# gatedriver_trafo_sma.net
KiCad netlist of a schematic drawn in EAGLE
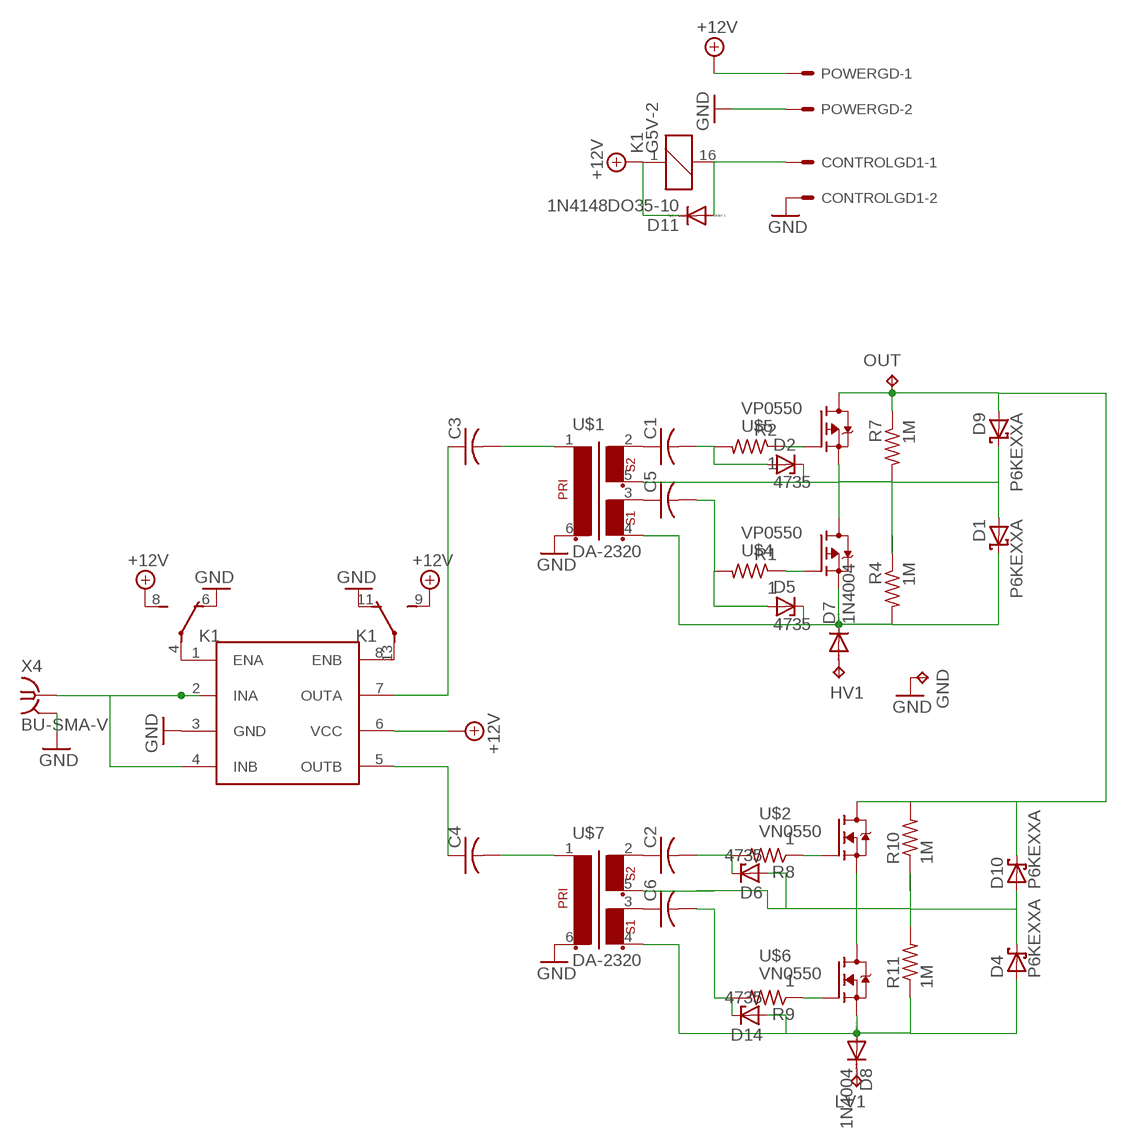
[diagram p0: schematic, sheet 1]

(export (version "E")
  (design (tool "Eeschema 10.0.6"))
  (components
    (comp (ref "C1")
      (value "C-US050-055X075")
      (footprint "eagle-import:C050-055X075")
      (libsource (lib "eagle-import") (part "C-US050-055X075"))
    )
    (comp (ref "C2")
      (value "C-US050-055X075")
      (footprint "eagle-import:C050-055X075")
      (libsource (lib "eagle-import") (part "C-US050-055X075"))
    )
    (comp (ref "C3")
      (value "C-US050-055X075")
      (footprint "eagle-import:C050-055X075")
      (libsource (lib "eagle-import") (part "C-US050-055X075"))
    )
    (comp (ref "C4")
      (value "C-US050-055X075")
      (footprint "eagle-import:C050-055X075")
      (libsource (lib "eagle-import") (part "C-US050-055X075"))
    )
    (comp (ref "C5")
      (value "C-US050-055X075")
      (footprint "eagle-import:C050-055X075")
      (libsource (lib "eagle-import") (part "C-US050-055X075"))
    )
    (comp (ref "C6")
      (value "C-US050-055X075")
      (footprint "eagle-import:C050-055X075")
      (libsource (lib "eagle-import") (part "C-US050-055X075"))
    )
    (comp (ref "CONTROLGD1")
      (value "KK-156-2")
      (footprint "eagle-import:KK-156-2")
      (libsource (lib "eagle-import") (part "KK-156-2"))
    )
    (comp (ref "D1")
      (value "P6KEXXA")
      (footprint "eagle-import:C1702-15")
      (libsource (lib "eagle-import") (part "P6KEXXA"))
    )
    (comp (ref "D2")
      (value "4735")
      (footprint "eagle-import:ZDIO-10")
      (libsource (lib "eagle-import") (part "ZENER-DIODEZD-10"))
    )
    (comp (ref "D4")
      (value "P6KEXXA")
      (footprint "eagle-import:C1702-15")
      (libsource (lib "eagle-import") (part "P6KEXXA"))
    )
    (comp (ref "D5")
      (value "4735")
      (footprint "eagle-import:ZDIO-10")
      (libsource (lib "eagle-import") (part "ZENER-DIODEZD-10"))
    )
    (comp (ref "D6")
      (value "4735")
      (footprint "eagle-import:ZDIO-10")
      (libsource (lib "eagle-import") (part "ZENER-DIODEZD-10"))
    )
    (comp (ref "D7")
      (value "1N4004")
      (footprint "eagle-import:DO41-10")
      (libsource (lib "eagle-import") (part "1N4004"))
    )
    (comp (ref "D8")
      (value "1N4004")
      (footprint "eagle-import:DO41-10")
      (libsource (lib "eagle-import") (part "1N4004"))
    )
    (comp (ref "D9")
      (value "P6KEXXA")
      (footprint "eagle-import:C1702-15")
      (libsource (lib "eagle-import") (part "P6KEXXA"))
    )
    (comp (ref "D10")
      (value "P6KEXXA")
      (footprint "eagle-import:C1702-15")
      (libsource (lib "eagle-import") (part "P6KEXXA"))
    )
    (comp (ref "D11")
      (value "1N4148DO35-10")
      (footprint "eagle-import:DO35-10")
      (libsource (lib "eagle-import") (part "1N4148DO35-10"))
    )
    (comp (ref "D14")
      (value "4735")
      (footprint "eagle-import:ZDIO-10")
      (libsource (lib "eagle-import") (part "ZENER-DIODEZD-10"))
    )
    (comp (ref "GND")
      (value "TPPAD1-20Y")
      (footprint "eagle-import:P1-20Y")
      (libsource (lib "eagle-import") (part "TPPAD1-20Y"))
    )
    (comp (ref "HV1")
      (value "TPPAD1-20Y")
      (footprint "eagle-import:P1-20Y")
      (libsource (lib "eagle-import") (part "TPPAD1-20Y"))
    )
    (comp (ref "K1")
      (value "G5V-2")
      (footprint "eagle-import:G5V-2")
      (fields (field (name "MPN") "G5V-2 5DC"))
      (libsource (lib "eagle-import") (part "G5V-2"))
    )
    (comp (ref "LV1")
      (value "TPPAD1-20Y")
      (footprint "eagle-import:P1-20Y")
      (libsource (lib "eagle-import") (part "TPPAD1-20Y"))
    )
    (comp (ref "OUT")
      (value "TPPAD1-20Y")
      (footprint "eagle-import:P1-20Y")
      (libsource (lib "eagle-import") (part "TPPAD1-20Y"))
    )
    (comp (ref "POWERGD")
      (value "KK-156-2")
      (footprint "eagle-import:KK-156-2")
      (libsource (lib "eagle-import") (part "KK-156-2"))
    )
    (comp (ref "R1")
      (value "1")
      (footprint "eagle-import:0207_12")
      (libsource (lib "eagle-import") (part "R-US_0207/12"))
    )
    (comp (ref "R2")
      (value "1")
      (footprint "eagle-import:0207_12")
      (libsource (lib "eagle-import") (part "R-US_0207/12"))
    )
    (comp (ref "R4")
      (value "1M")
      (footprint "eagle-import:0207_12")
      (libsource (lib "eagle-import") (part "R-US_0207/12"))
    )
    (comp (ref "R7")
      (value "1M")
      (footprint "eagle-import:0207_12")
      (libsource (lib "eagle-import") (part "R-US_0207/12"))
    )
    (comp (ref "R8")
      (value "1")
      (footprint "eagle-import:0207_12")
      (libsource (lib "eagle-import") (part "R-US_0207/12"))
    )
    (comp (ref "R9")
      (value "1")
      (footprint "eagle-import:0207_12")
      (libsource (lib "eagle-import") (part "R-US_0207/12"))
    )
    (comp (ref "R10")
      (value "1M")
      (footprint "eagle-import:0207_12")
      (libsource (lib "eagle-import") (part "R-US_0207/12"))
    )
    (comp (ref "R11")
      (value "1M")
      (footprint "eagle-import:0207_12")
      (libsource (lib "eagle-import") (part "R-US_0207/12"))
    )
    (comp (ref "U$1")
      (value "DA-2320")
      (footprint "eagle-import:DIL06")
      (libsource (lib "eagle-import") (part "DA-2320"))
    )
    (comp (ref "U$2")
      (value "VN0550")
      (footprint "eagle-import:TO92-")
      (libsource (lib "eagle-import") (part "VN0550"))
    )
    (comp (ref "U$3")
      (value "UCC27425")
      (footprint "eagle-import:DIL08")
      (libsource (lib "eagle-import") (part "UCC27425"))
    )
    (comp (ref "U$4")
      (value "VP0550")
      (footprint "eagle-import:TO92-")
      (libsource (lib "eagle-import") (part "VP0550"))
    )
    (comp (ref "U$5")
      (value "VP0550")
      (footprint "eagle-import:TO92-")
      (libsource (lib "eagle-import") (part "VP0550"))
    )
    (comp (ref "U$6")
      (value "VN0550")
      (footprint "eagle-import:TO92-")
      (libsource (lib "eagle-import") (part "VN0550"))
    )
    (comp (ref "U$7")
      (value "DA-2320")
      (footprint "eagle-import:DIL06")
      (libsource (lib "eagle-import") (part "DA-2320"))
    )
    (comp (ref "X4")
      (value "BU-SMA-V")
      (footprint "eagle-import:BU-SMA-V")
      (libsource (lib "eagle-import") (part "BU-SMA-V"))
    )
  )
  (nets
    (net (code "1") (name "+12V") (class "Default")
      (node (ref "D11") (pin "C") (pinfunction "C_C") (pintype "passive"))
      (node (ref "K1") (pin "1") (pinfunction "1_1") (pintype "passive"))
      (node (ref "K1") (pin "8") (pinfunction "S_8") (pintype "passive"))
      (node (ref "K1") (pin "9") (pinfunction "S_9") (pintype "passive"))
      (node (ref "POWERGD") (pin "1") (pinfunction "S_1") (pintype "passive"))
      (node (ref "U$3") (pin "6") (pinfunction "VCC_6") (pintype "bidirectional"))
    )
    (net (code "2") (name "/N$17") (class "Default")
      (node (ref "D1") (pin "C") (pinfunction "C_C") (pintype "passive"))
      (node (ref "D5") (pin "C") (pinfunction "C_C") (pintype "passive"))
      (node (ref "D7") (pin "C") (pinfunction "C_C") (pintype "passive"))
      (node (ref "R4") (pin "2") (pinfunction "2_2") (pintype "passive"))
      (node (ref "U$1") (pin "4") (pinfunction "3_4") (pintype "passive"))
      (node (ref "U$4") (pin "3") (pinfunction "S_3") (pintype "passive"))
    )
    (net (code "3") (name "GND") (class "Default")
      (node (ref "CONTROLGD1") (pin "2") (pinfunction "S_2") (pintype "passive"))
      (node (ref "GND") (pin "TP") (pinfunction "TP_TP") (pintype "input"))
      (node (ref "K1") (pin "11") (pinfunction "O_11") (pintype "passive"))
      (node (ref "K1") (pin "6") (pinfunction "O_6") (pintype "passive"))
      (node (ref "POWERGD") (pin "2") (pinfunction "S_2") (pintype "passive"))
      (node (ref "U$1") (pin "6") (pinfunction "2_6") (pintype "passive"))
      (node (ref "U$3") (pin "3") (pinfunction "GND_3") (pintype "bidirectional"))
      (node (ref "U$7") (pin "6") (pinfunction "2_6") (pintype "passive"))
      (node (ref "X4") (pin "2") (pinfunction "2_2") (pintype "passive"))
      (node (ref "X4") (pin "3") (pinfunction "2_3") (pintype "passive"))
      (node (ref "X4") (pin "4") (pinfunction "2_4") (pintype "passive"))
      (node (ref "X4") (pin "5") (pinfunction "2_5") (pintype "passive"))
    )
    (net (code "4") (name "Net-(C1-Pad2)") (class "Default")
      (node (ref "C1") (pin "2") (pinfunction "2_2") (pintype "passive"))
      (node (ref "D2") (pin "A") (pinfunction "A_A") (pintype "passive"))
      (node (ref "R2") (pin "2") (pinfunction "2_2") (pintype "passive"))
    )
    (net (code "5") (name "Net-(C2-Pad2)") (class "Default")
      (node (ref "C2") (pin "2") (pinfunction "2_2") (pintype "passive"))
      (node (ref "D6") (pin "C") (pinfunction "C_C") (pintype "passive"))
      (node (ref "R8") (pin "2") (pinfunction "2_2") (pintype "passive"))
    )
    (net (code "6") (name "Net-(C3-Pad2)") (class "Default")
      (node (ref "C3") (pin "2") (pinfunction "2_2") (pintype "passive"))
      (node (ref "U$1") (pin "1") (pinfunction "1_1") (pintype "passive"))
    )
    (net (code "7") (name "Net-(C4-Pad2)") (class "Default")
      (node (ref "C4") (pin "2") (pinfunction "2_2") (pintype "passive"))
      (node (ref "U$7") (pin "1") (pinfunction "1_1") (pintype "passive"))
    )
    (net (code "8") (name "Net-(C5-Pad2)") (class "Default")
      (node (ref "C5") (pin "2") (pinfunction "2_2") (pintype "passive"))
      (node (ref "D5") (pin "A") (pinfunction "A_A") (pintype "passive"))
      (node (ref "R1") (pin "2") (pinfunction "2_2") (pintype "passive"))
    )
    (net (code "9") (name "Net-(C6-Pad2)") (class "Default")
      (node (ref "C6") (pin "2") (pinfunction "2_2") (pintype "passive"))
      (node (ref "D14") (pin "C") (pinfunction "C_C") (pintype "passive"))
      (node (ref "R9") (pin "2") (pinfunction "2_2") (pintype "passive"))
    )
    (net (code "10") (name "Net-(CONTROLGD1A-S)") (class "Default")
      (node (ref "CONTROLGD1") (pin "1") (pinfunction "S_1") (pintype "passive"))
      (node (ref "D11") (pin "A") (pinfunction "A_A") (pintype "passive"))
      (node (ref "K1") (pin "16") (pinfunction "2_16") (pintype "passive"))
    )
    (net (code "11") (name "Net-(D7-PadA)") (class "Default")
      (node (ref "D7") (pin "A") (pinfunction "A_A") (pintype "passive"))
      (node (ref "HV1") (pin "TP") (pinfunction "TP_TP") (pintype "input"))
    )
    (net (code "12") (name "Net-(D8-PadC)") (class "Default")
      (node (ref "D8") (pin "C") (pinfunction "C_C") (pintype "passive"))
      (node (ref "LV1") (pin "TP") (pinfunction "TP_TP") (pintype "input"))
    )
    (net (code "13") (name "Net-(K1A-P)") (class "Default")
      (node (ref "K1") (pin "4") (pinfunction "P_4") (pintype "passive"))
      (node (ref "U$3") (pin "1") (pinfunction "ENA_1") (pintype "bidirectional"))
    )
    (net (code "14") (name "Net-(K1B-P)") (class "Default")
      (node (ref "K1") (pin "13") (pinfunction "P_13") (pintype "passive"))
      (node (ref "U$3") (pin "8") (pinfunction "ENB_8") (pintype "bidirectional"))
    )
    (net (code "15") (name "Net-(U$1-4)") (class "Default")
      (node (ref "C5") (pin "1") (pinfunction "1_1") (pintype "passive"))
      (node (ref "U$1") (pin "3") (pinfunction "4_3") (pintype "passive"))
    )
    (net (code "16") (name "Net-(U$1-6)") (class "Default")
      (node (ref "C1") (pin "1") (pinfunction "1_1") (pintype "passive"))
      (node (ref "U$1") (pin "2") (pinfunction "6_2") (pintype "passive"))
    )
    (net (code "17") (name "Net-(U$2-D)") (class "Default")
      (node (ref "D10") (pin "C") (pinfunction "C_C") (pintype "passive"))
      (node (ref "D9") (pin "A") (pinfunction "A_A") (pintype "passive"))
      (node (ref "OUT") (pin "TP") (pinfunction "TP_TP") (pintype "input"))
      (node (ref "R10") (pin "2") (pinfunction "2_2") (pintype "passive"))
      (node (ref "R7") (pin "1") (pinfunction "1_1") (pintype "passive"))
      (node (ref "U$2") (pin "1") (pinfunction "D_1") (pintype "passive"))
      (node (ref "U$5") (pin "1") (pinfunction "D_1") (pintype "passive"))
    )
    (net (code "18") (name "Net-(U$2-G)") (class "Default")
      (node (ref "R8") (pin "1") (pinfunction "1_1") (pintype "passive"))
      (node (ref "U$2") (pin "2") (pinfunction "G_2") (pintype "passive"))
    )
    (net (code "19") (name "Net-(U$2-S)") (class "Default")
      (node (ref "D10") (pin "A") (pinfunction "A_A") (pintype "passive"))
      (node (ref "D4") (pin "C") (pinfunction "C_C") (pintype "passive"))
      (node (ref "D6") (pin "A") (pinfunction "A_A") (pintype "passive"))
      (node (ref "R10") (pin "1") (pinfunction "1_1") (pintype "passive"))
      (node (ref "R11") (pin "2") (pinfunction "2_2") (pintype "passive"))
      (node (ref "U$2") (pin "3") (pinfunction "S_3") (pintype "passive"))
      (node (ref "U$6") (pin "1") (pinfunction "D_1") (pintype "passive"))
    )
    (net (code "20") (name "Net-(U$3-INA)") (class "Default")
      (node (ref "U$3") (pin "2") (pinfunction "INA_2") (pintype "bidirectional"))
      (node (ref "U$3") (pin "4") (pinfunction "INB_4") (pintype "bidirectional"))
      (node (ref "X4") (pin "1") (pinfunction "1_1") (pintype "passive"))
    )
    (net (code "21") (name "Net-(U$3-OUTA)") (class "Default")
      (node (ref "C3") (pin "1") (pinfunction "1_1") (pintype "passive"))
      (node (ref "U$3") (pin "7") (pinfunction "OUTA_7") (pintype "bidirectional"))
    )
    (net (code "22") (name "Net-(U$3-OUTB)") (class "Default")
      (node (ref "C4") (pin "1") (pinfunction "1_1") (pintype "passive"))
      (node (ref "U$3") (pin "5") (pinfunction "OUTB_5") (pintype "bidirectional"))
    )
    (net (code "23") (name "Net-(U$4-D)") (class "Default")
      (node (ref "D1") (pin "A") (pinfunction "A_A") (pintype "passive"))
      (node (ref "D2") (pin "C") (pinfunction "C_C") (pintype "passive"))
      (node (ref "D9") (pin "C") (pinfunction "C_C") (pintype "passive"))
      (node (ref "R4") (pin "1") (pinfunction "1_1") (pintype "passive"))
      (node (ref "R7") (pin "2") (pinfunction "2_2") (pintype "passive"))
      (node (ref "U$1") (pin "5") (pinfunction "5_5") (pintype "passive"))
      (node (ref "U$4") (pin "1") (pinfunction "D_1") (pintype "passive"))
      (node (ref "U$5") (pin "3") (pinfunction "S_3") (pintype "passive"))
    )
    (net (code "24") (name "Net-(U$4-G)") (class "Default")
      (node (ref "R1") (pin "1") (pinfunction "1_1") (pintype "passive"))
      (node (ref "U$4") (pin "2") (pinfunction "G_2") (pintype "passive"))
    )
    (net (code "25") (name "Net-(U$5-G)") (class "Default")
      (node (ref "R2") (pin "1") (pinfunction "1_1") (pintype "passive"))
      (node (ref "U$5") (pin "2") (pinfunction "G_2") (pintype "passive"))
    )
    (net (code "26") (name "Net-(U$6-G)") (class "Default")
      (node (ref "R9") (pin "1") (pinfunction "1_1") (pintype "passive"))
      (node (ref "U$6") (pin "2") (pinfunction "G_2") (pintype "passive"))
    )
    (net (code "27") (name "Net-(U$6-S)") (class "Default")
      (node (ref "D14") (pin "A") (pinfunction "A_A") (pintype "passive"))
      (node (ref "D4") (pin "A") (pinfunction "A_A") (pintype "passive"))
      (node (ref "D8") (pin "A") (pinfunction "A_A") (pintype "passive"))
      (node (ref "R11") (pin "1") (pinfunction "1_1") (pintype "passive"))
      (node (ref "U$6") (pin "3") (pinfunction "S_3") (pintype "passive"))
      (node (ref "U$7") (pin "4") (pinfunction "3_4") (pintype "passive"))
    )
    (net (code "28") (name "Net-(U$7-4)") (class "Default")
      (node (ref "C6") (pin "1") (pinfunction "1_1") (pintype "passive"))
      (node (ref "U$7") (pin "3") (pinfunction "4_3") (pintype "passive"))
    )
    (net (code "29") (name "Net-(U$7-6)") (class "Default")
      (node (ref "C2") (pin "1") (pinfunction "1_1") (pintype "passive"))
      (node (ref "U$7") (pin "2") (pinfunction "6_2") (pintype "passive"))
    )
    (net (code "30") (name "unconnected-(U$7-Pad5)") (class "Default")
      (node (ref "U$7") (pin "5") (pinfunction "5_5") (pintype "passive"))
    )
  )
)
